# demux_smd.net
KiCad netlist of a schematic drawn in EAGLE
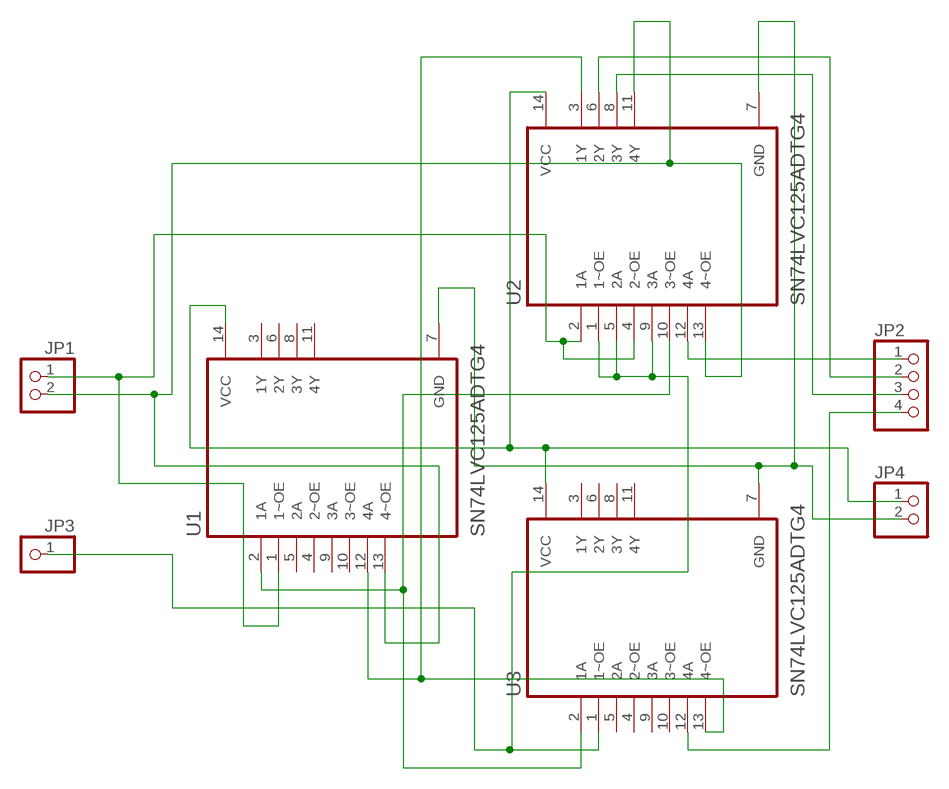
[diagram p0: schematic, sheet 1]

(export (version "E")
  (design (tool "Eeschema 10.0.6"))
  (components
    (comp (ref "JP1")
      (value "PINHD-1X2")
      (footprint "eagle-import:1X02")
      (libsource (lib "eagle-import") (part "PINHD-1X2"))
    )
    (comp (ref "JP2")
      (value "PINHD-1X4")
      (footprint "eagle-import:1X04")
      (libsource (lib "eagle-import") (part "PINHD-1X4"))
    )
    (comp (ref "JP3")
      (value "PINHD-1X1")
      (footprint "eagle-import:1X01")
      (libsource (lib "eagle-import") (part "PINHD-1X1"))
    )
    (comp (ref "JP4")
      (value "PINHD-1X2")
      (footprint "eagle-import:1X02")
      (libsource (lib "eagle-import") (part "PINHD-1X2"))
    )
    (comp (ref "U1")
      (value "SN74LVC125ADTG4")
      (footprint "eagle-import:SOIC127P600X175-14N")
      (fields (field (name "MF") "Texas Instruments"))
      (libsource (lib "eagle-import") (part "SN74LVC125ADTG4"))
    )
    (comp (ref "U2")
      (value "SN74LVC125ADTG4")
      (footprint "eagle-import:SOIC127P600X175-14N")
      (fields (field (name "MF") "Texas Instruments"))
      (libsource (lib "eagle-import") (part "SN74LVC125ADTG4"))
    )
    (comp (ref "U3")
      (value "SN74LVC125ADTG4")
      (footprint "eagle-import:SOIC127P600X175-14N")
      (fields (field (name "MF") "Texas Instruments"))
      (libsource (lib "eagle-import") (part "SN74LVC125ADTG4"))
    )
  )
  (nets
    (net (code "1") (name "Net-(U1-1A)") (class "Default")
      (node (ref "U1") (pin "2") (pinfunction "1A_2") (pintype "input"))
      (node (ref "U2") (pin "10") (pinfunction "3~{OE}_10") (pintype "input"))
      (node (ref "U3") (pin "2") (pinfunction "1A_2") (pintype "input"))
    )
    (net (code "2") (name "Net-(U1-1~{OE})") (class "Default")
      (node (ref "JP1") (pin "1") (pinfunction "1_1") (pintype "passive"))
      (node (ref "U1") (pin "1") (pinfunction "1~{OE}_1") (pintype "input"))
      (node (ref "U2") (pin "2") (pinfunction "1A_2") (pintype "input"))
      (node (ref "U2") (pin "4") (pinfunction "2~{OE}_4") (pintype "input"))
    )
    (net (code "3") (name "Net-(U1-4A)") (class "Default")
      (node (ref "U1") (pin "12") (pinfunction "4A_12") (pintype "input"))
      (node (ref "U2") (pin "3") (pinfunction "1Y_3") (pintype "output"))
      (node (ref "U3") (pin "13") (pinfunction "4~{OE}_13") (pintype "input"))
    )
    (net (code "4") (name "Net-(U1-4~{OE})") (class "Default")
      (node (ref "JP1") (pin "2") (pinfunction "2_2") (pintype "passive"))
      (node (ref "U1") (pin "13") (pinfunction "4~{OE}_13") (pintype "input"))
      (node (ref "U2") (pin "11") (pinfunction "4Y_11") (pintype "output"))
      (node (ref "U2") (pin "13") (pinfunction "4~{OE}_13") (pintype "input"))
    )
    (net (code "5") (name "Net-(U1-GND)") (class "Default")
      (node (ref "JP4") (pin "2") (pinfunction "2_2") (pintype "passive"))
      (node (ref "U1") (pin "7") (pinfunction "GND_7") (pintype "power_in"))
      (node (ref "U2") (pin "7") (pinfunction "GND_7") (pintype "power_in"))
      (node (ref "U3") (pin "7") (pinfunction "GND_7") (pintype "power_in"))
    )
    (net (code "6") (name "Net-(U1-VCC)") (class "Default")
      (node (ref "JP4") (pin "1") (pinfunction "1_1") (pintype "passive"))
      (node (ref "U1") (pin "14") (pinfunction "VCC_14") (pintype "power_in"))
      (node (ref "U2") (pin "14") (pinfunction "VCC_14") (pintype "power_in"))
      (node (ref "U3") (pin "14") (pinfunction "VCC_14") (pintype "power_in"))
    )
    (net (code "7") (name "Net-(U2-1~{OE})") (class "Default")
      (node (ref "JP3") (pin "1") (pinfunction "1_1") (pintype "passive"))
      (node (ref "U2") (pin "1") (pinfunction "1~{OE}_1") (pintype "input"))
      (node (ref "U2") (pin "5") (pinfunction "2A_5") (pintype "input"))
      (node (ref "U2") (pin "9") (pinfunction "3A_9") (pintype "input"))
      (node (ref "U3") (pin "1") (pinfunction "1~{OE}_1") (pintype "input"))
    )
    (net (code "8") (name "Net-(U2-2Y)") (class "Default")
      (node (ref "JP2") (pin "2") (pinfunction "2_2") (pintype "passive"))
      (node (ref "U2") (pin "6") (pinfunction "2Y_6") (pintype "output"))
    )
    (net (code "9") (name "Net-(U2-3Y)") (class "Default")
      (node (ref "JP2") (pin "3") (pinfunction "3_3") (pintype "passive"))
      (node (ref "U2") (pin "8") (pinfunction "3Y_8") (pintype "output"))
    )
    (net (code "10") (name "Net-(U2-4A)") (class "Default")
      (node (ref "JP2") (pin "1") (pinfunction "1_1") (pintype "passive"))
      (node (ref "U2") (pin "12") (pinfunction "4A_12") (pintype "input"))
    )
    (net (code "11") (name "Net-(U3-4A)") (class "Default")
      (node (ref "JP2") (pin "4") (pinfunction "4_4") (pintype "passive"))
      (node (ref "U3") (pin "12") (pinfunction "4A_12") (pintype "input"))
    )
    (net (code "12") (name "unconnected-(U1-1Y-Pad3)") (class "Default")
      (node (ref "U1") (pin "3") (pinfunction "1Y_3") (pintype "output"))
    )
    (net (code "13") (name "unconnected-(U1-2A-Pad5)") (class "Default")
      (node (ref "U1") (pin "5") (pinfunction "2A_5") (pintype "input"))
    )
    (net (code "14") (name "unconnected-(U1-2Y-Pad6)") (class "Default")
      (node (ref "U1") (pin "6") (pinfunction "2Y_6") (pintype "output"))
    )
    (net (code "15") (name "unconnected-(U1-2~{OE}-Pad4)") (class "Default")
      (node (ref "U1") (pin "4") (pinfunction "2~{OE}_4") (pintype "input"))
    )
    (net (code "16") (name "unconnected-(U1-3A-Pad9)") (class "Default")
      (node (ref "U1") (pin "9") (pinfunction "3A_9") (pintype "input"))
    )
    (net (code "17") (name "unconnected-(U1-3Y-Pad8)") (class "Default")
      (node (ref "U1") (pin "8") (pinfunction "3Y_8") (pintype "output"))
    )
    (net (code "18") (name "unconnected-(U1-3~{OE}-Pad10)") (class "Default")
      (node (ref "U1") (pin "10") (pinfunction "3~{OE}_10") (pintype "input"))
    )
    (net (code "19") (name "unconnected-(U1-4Y-Pad11)") (class "Default")
      (node (ref "U1") (pin "11") (pinfunction "4Y_11") (pintype "output"))
    )
    (net (code "20") (name "unconnected-(U3-1Y-Pad3)") (class "Default")
      (node (ref "U3") (pin "3") (pinfunction "1Y_3") (pintype "output"))
    )
    (net (code "21") (name "unconnected-(U3-2A-Pad5)") (class "Default")
      (node (ref "U3") (pin "5") (pinfunction "2A_5") (pintype "input"))
    )
    (net (code "22") (name "unconnected-(U3-2Y-Pad6)") (class "Default")
      (node (ref "U3") (pin "6") (pinfunction "2Y_6") (pintype "output"))
    )
    (net (code "23") (name "unconnected-(U3-2~{OE}-Pad4)") (class "Default")
      (node (ref "U3") (pin "4") (pinfunction "2~{OE}_4") (pintype "input"))
    )
    (net (code "24") (name "unconnected-(U3-3A-Pad9)") (class "Default")
      (node (ref "U3") (pin "9") (pinfunction "3A_9") (pintype "input"))
    )
    (net (code "25") (name "unconnected-(U3-3Y-Pad8)") (class "Default")
      (node (ref "U3") (pin "8") (pinfunction "3Y_8") (pintype "output"))
    )
    (net (code "26") (name "unconnected-(U3-3~{OE}-Pad10)") (class "Default")
      (node (ref "U3") (pin "10") (pinfunction "3~{OE}_10") (pintype "input"))
    )
    (net (code "27") (name "unconnected-(U3-4Y-Pad11)") (class "Default")
      (node (ref "U3") (pin "11") (pinfunction "4Y_11") (pintype "output"))
    )
  )
)
